# FNC_Necklace.net
KiCad netlist of a schematic drawn in Altium Designer
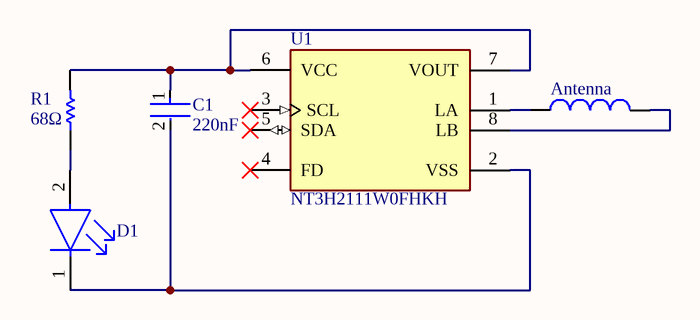
[diagram p0: FNC_Necklace.SchDoc]

(export (version "E")
  (design (tool "Eeschema 10.0.6"))
  (components
    (comp (ref "Antenna")
      (value "NFC_antenna")
      (footprint "NFC_antenna-Footprint-1")
      (libsource (lib "Autonomy Lab") (part "NFC_antenna-Symbol-1"))
    )
    (comp (ref "C1")
      (value "GRM155R71C224KA12D")
      (footprint "FP-GRM155-0_05-IPC_C")
      (description "Chip Multilayer Ceramic Capacitors for General Purpose, 0402, 0.22uF, X7R, 15%, 10%, 16V")
      (fields
        (field (name "CAPACITANCE") "220nF")
        (field (name "VOLTAGE") "16V")
        (field (name "TOLERANCE") "10%")
      )
      (libsource (lib "Altium Content Vault") (part "02cd4be3c70576c341d710602a673aa"))
    )
    (comp (ref "D1")
      (value "LO L29K-J2L1-24-Z")
      (footprint "FP-LO_L29K-MFG")
      (description "LED ORANGE DIFFUSED 0603 SMD")
      (libsource (lib "Altium Content Vault") (part "8706943c75ba83719d021d2fdc84c58"))
    )
    (comp (ref "R1")
      (value "CRCW060368R0FKEA")
      (footprint "RESC1609X50X30LL10T20")
      (fields (field (name "MANUFACTURER") "Vishay Dale") (field (name "RESISTANCE") "68Ω"))
      (libsource (lib "Altium Content Vault") (part "RES"))
    )
    (comp (ref "U1")
      (value "NT3H2111W0FHKH")
      (footprint "FP-SOT902-3-MFG")
      (description "IC RFID TRANSP 13.56MHZ 8XQFN")
      (fields
        (field (name "MANUFACTURER") "NXP")
        (field (name "OCTOPART") "https://octopart.com/nt3h2111w0fhkh-nxp+semiconductors-71112033")
      )
      (libsource (lib "Altium Content Vault") (part "39eb1c674dcfd8f95a63d21f9f9692a"))
    )
  )
  (nets
    (net (code "1") (name "Net-(D1-A)") (class "Default")
      (node (ref "D1") (pin "2") (pinfunction "A_2") (pintype "passive"))
      (node (ref "R1") (pin "1") (pinfunction "1_1") (pintype "passive"))
    )
    (net (code "2") (name "Net-(D1-C)") (class "Default")
      (node (ref "C1") (pin "2") (pinfunction "2_2") (pintype "passive"))
      (node (ref "D1") (pin "1") (pinfunction "C_1") (pintype "passive"))
      (node (ref "U1") (pin "2") (pinfunction "VSS_2") (pintype "power_in"))
    )
    (net (code "3") (name "Net-(U1-LA)") (class "Default")
      (node (ref "Antenna") (pin "1") (pinfunction "1_1") (pintype "passive"))
      (node (ref "U1") (pin "1") (pinfunction "LA_1") (pintype "passive"))
    )
    (net (code "4") (name "Net-(U1-LB)") (class "Default")
      (node (ref "Antenna") (pin "2") (pinfunction "2_2") (pintype "passive"))
      (node (ref "U1") (pin "8") (pinfunction "LB_8") (pintype "passive"))
    )
    (net (code "5") (name "Net-(U1-VCC)") (class "Default")
      (node (ref "C1") (pin "1") (pinfunction "1_1") (pintype "passive"))
      (node (ref "R1") (pin "2") (pinfunction "2_2") (pintype "passive"))
      (node (ref "U1") (pin "6") (pinfunction "VCC_6") (pintype "power_in"))
      (node (ref "U1") (pin "7") (pinfunction "VOUT_7") (pintype "power_in"))
    )
    (net (code "6") (name "unconnected-(U1-FD-Pad4)") (class "Default")
      (node (ref "U1") (pin "4") (pinfunction "FD_4") (pintype "passive+no_connect"))
    )
    (net (code "7") (name "unconnected-(U1-SCL-Pad3)") (class "Default")
      (node (ref "U1") (pin "3") (pinfunction "SCL_3") (pintype "input+no_connect"))
    )
    (net (code "8") (name "unconnected-(U1-SDA-Pad5)") (class "Default")
      (node (ref "U1") (pin "5") (pinfunction "SDA_5") (pintype "bidirectional+no_connect"))
    )
  )
)
